# ESP32_LS7366.net
KiCad netlist of a schematic drawn in EAGLE
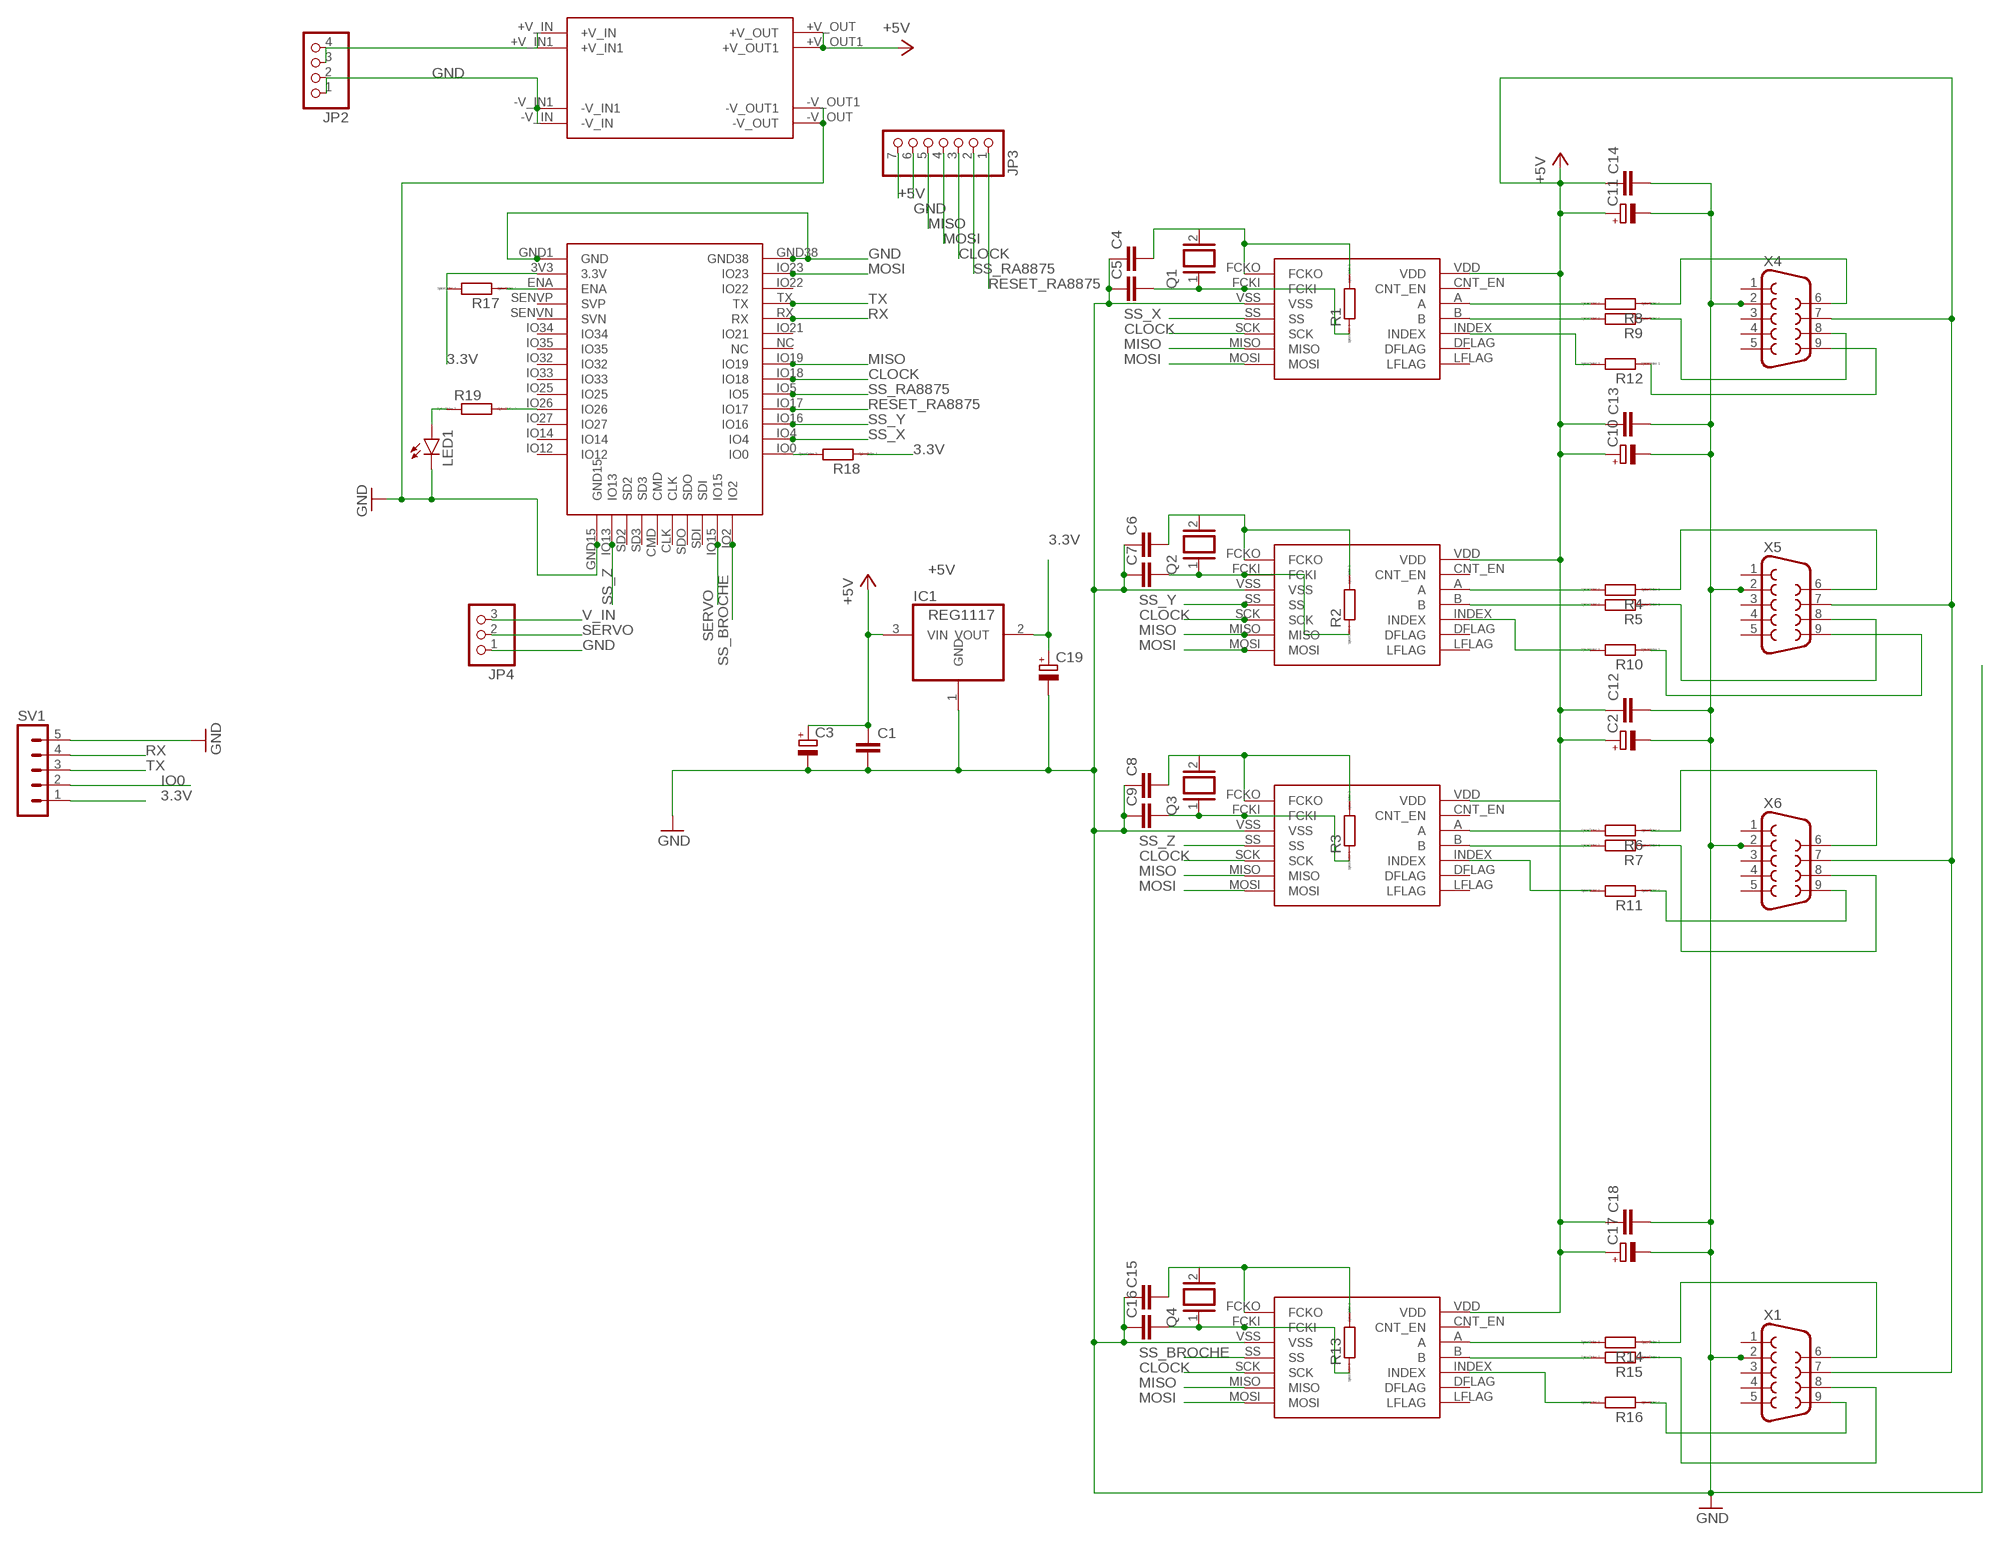
[diagram p0: schematic, sheet 1]

(export (version "E")
  (design (tool "Eeschema 10.0.6"))
  (components
    (comp (ref "C1")
      (value "C-EU050-035X075")
      (footprint "eagle-import:C050-035X075")
      (libsource (lib "eagle-import") (part "C-EU050-035X075"))
    )
    (comp (ref "C2")
      (value "CPOL-EUE5-5")
      (footprint "eagle-import:E5-5")
      (libsource (lib "eagle-import") (part "CPOL-EUE5-5"))
    )
    (comp (ref "C3")
      (value "CPOL-EUE5-5")
      (footprint "eagle-import:E5-5")
      (libsource (lib "eagle-import") (part "CPOL-EUE5-5"))
    )
    (comp (ref "C4")
      (value "C2.5/5")
      (footprint "eagle-import:C2.5-5")
      (libsource (lib "eagle-import") (part "C2.5/5"))
    )
    (comp (ref "C5")
      (value "C2.5/5")
      (footprint "eagle-import:C2.5-5")
      (libsource (lib "eagle-import") (part "C2.5/5"))
    )
    (comp (ref "C6")
      (value "C2.5/5")
      (footprint "eagle-import:C2.5-5")
      (libsource (lib "eagle-import") (part "C2.5/5"))
    )
    (comp (ref "C7")
      (value "C2.5/5")
      (footprint "eagle-import:C2.5-5")
      (libsource (lib "eagle-import") (part "C2.5/5"))
    )
    (comp (ref "C8")
      (value "C2.5/5")
      (footprint "eagle-import:C2.5-5")
      (libsource (lib "eagle-import") (part "C2.5/5"))
    )
    (comp (ref "C9")
      (value "C2.5/5")
      (footprint "eagle-import:C2.5-5")
      (libsource (lib "eagle-import") (part "C2.5/5"))
    )
    (comp (ref "C10")
      (value "CPOL-EUE5-5")
      (footprint "eagle-import:E5-5")
      (libsource (lib "eagle-import") (part "CPOL-EUE5-5"))
    )
    (comp (ref "C11")
      (value "CPOL-EUE5-5")
      (footprint "eagle-import:E5-5")
      (libsource (lib "eagle-import") (part "CPOL-EUE5-5"))
    )
    (comp (ref "C12")
      (value "C-EU050-035X075")
      (footprint "eagle-import:C050-035X075")
      (libsource (lib "eagle-import") (part "C-EU050-035X075"))
    )
    (comp (ref "C13")
      (value "C-EU050-035X075")
      (footprint "eagle-import:C050-035X075")
      (libsource (lib "eagle-import") (part "C-EU050-035X075"))
    )
    (comp (ref "C14")
      (value "C-EU050-035X075")
      (footprint "eagle-import:C050-035X075")
      (libsource (lib "eagle-import") (part "C-EU050-035X075"))
    )
    (comp (ref "C15")
      (value "C2.5/5")
      (footprint "eagle-import:C2.5-5")
      (libsource (lib "eagle-import") (part "C2.5/5"))
    )
    (comp (ref "C16")
      (value "C2.5/5")
      (footprint "eagle-import:C2.5-5")
      (libsource (lib "eagle-import") (part "C2.5/5"))
    )
    (comp (ref "C17")
      (value "CPOL-EUE5-5")
      (footprint "eagle-import:E5-5")
      (libsource (lib "eagle-import") (part "CPOL-EUE5-5"))
    )
    (comp (ref "C18")
      (value "C-EU050-035X075")
      (footprint "eagle-import:C050-035X075")
      (libsource (lib "eagle-import") (part "C-EU050-035X075"))
    )
    (comp (ref "C19")
      (value "CPOL-EUE5-5")
      (footprint "eagle-import:E5-5")
      (libsource (lib "eagle-import") (part "CPOL-EUE5-5"))
    )
    (comp (ref "IC1")
      (value "REG1117")
      (footprint "eagle-import:SOT223")
      (libsource (lib "eagle-import") (part "REG1117"))
    )
    (comp (ref "JP2")
      (value "PINHD-1X4")
      (footprint "eagle-import:1X04")
      (libsource (lib "eagle-import") (part "PINHD-1X4"))
    )
    (comp (ref "JP3")
      (value "PINHD-1X7")
      (footprint "eagle-import:1X07")
      (libsource (lib "eagle-import") (part "PINHD-1X7"))
    )
    (comp (ref "JP4")
      (value "PINHD-1X3")
      (footprint "eagle-import:1X03")
      (libsource (lib "eagle-import") (part "PINHD-1X3"))
    )
    (comp (ref "LED1")
      (value "LED3MM")
      (footprint "eagle-import:LED3MM")
      (libsource (lib "eagle-import") (part "LED3MM"))
    )
    (comp (ref "Q1")
      (value "XTAL/S")
      (footprint "eagle-import:QS")
      (libsource (lib "eagle-import") (part "XTAL/S"))
    )
    (comp (ref "Q2")
      (value "XTAL/S")
      (footprint "eagle-import:QS")
      (libsource (lib "eagle-import") (part "XTAL/S"))
    )
    (comp (ref "Q3")
      (value "XTAL/S")
      (footprint "eagle-import:QS")
      (libsource (lib "eagle-import") (part "XTAL/S"))
    )
    (comp (ref "Q4")
      (value "XTAL/S")
      (footprint "eagle-import:QS")
      (libsource (lib "eagle-import") (part "XTAL/S"))
    )
    (comp (ref "R1")
      (value "R-EU_0207_10")
      (footprint "eagle-import:0207_10")
      (libsource (lib "eagle-import") (part "R-EU_0207_10"))
    )
    (comp (ref "R2")
      (value "R-EU_0207_10")
      (footprint "eagle-import:0207_10")
      (libsource (lib "eagle-import") (part "R-EU_0207_10"))
    )
    (comp (ref "R3")
      (value "R-EU_0207_10")
      (footprint "eagle-import:0207_10")
      (libsource (lib "eagle-import") (part "R-EU_0207_10"))
    )
    (comp (ref "R4")
      (value "R-EU_0207_10")
      (footprint "eagle-import:0207_10")
      (libsource (lib "eagle-import") (part "R-EU_0207_10"))
    )
    (comp (ref "R5")
      (value "R-EU_0207_10")
      (footprint "eagle-import:0207_10")
      (libsource (lib "eagle-import") (part "R-EU_0207_10"))
    )
    (comp (ref "R6")
      (value "R-EU_0207_10")
      (footprint "eagle-import:0207_10")
      (libsource (lib "eagle-import") (part "R-EU_0207_10"))
    )
    (comp (ref "R7")
      (value "R-EU_0207_10")
      (footprint "eagle-import:0207_10")
      (libsource (lib "eagle-import") (part "R-EU_0207_10"))
    )
    (comp (ref "R8")
      (value "R-EU_0207_10")
      (footprint "eagle-import:0207_10")
      (libsource (lib "eagle-import") (part "R-EU_0207_10"))
    )
    (comp (ref "R9")
      (value "R-EU_0207_10")
      (footprint "eagle-import:0207_10")
      (libsource (lib "eagle-import") (part "R-EU_0207_10"))
    )
    (comp (ref "R10")
      (value "R-EU_0207_10")
      (footprint "eagle-import:0207_10")
      (libsource (lib "eagle-import") (part "R-EU_0207_10"))
    )
    (comp (ref "R11")
      (value "R-EU_0207_10")
      (footprint "eagle-import:0207_10")
      (libsource (lib "eagle-import") (part "R-EU_0207_10"))
    )
    (comp (ref "R12")
      (value "R-EU_0207_10")
      (footprint "eagle-import:0207_10")
      (libsource (lib "eagle-import") (part "R-EU_0207_10"))
    )
    (comp (ref "R13")
      (value "R-EU_0207_10")
      (footprint "eagle-import:0207_10")
      (libsource (lib "eagle-import") (part "R-EU_0207_10"))
    )
    (comp (ref "R14")
      (value "R-EU_0207_10")
      (footprint "eagle-import:0207_10")
      (libsource (lib "eagle-import") (part "R-EU_0207_10"))
    )
    (comp (ref "R15")
      (value "R-EU_0207_10")
      (footprint "eagle-import:0207_10")
      (libsource (lib "eagle-import") (part "R-EU_0207_10"))
    )
    (comp (ref "R16")
      (value "R-EU_0207_10")
      (footprint "eagle-import:0207_10")
      (libsource (lib "eagle-import") (part "R-EU_0207_10"))
    )
    (comp (ref "R17")
      (value "R-EU_0207_10")
      (footprint "eagle-import:0207_10")
      (libsource (lib "eagle-import") (part "R-EU_0207_10"))
    )
    (comp (ref "R18")
      (value "R-EU_0207_10")
      (footprint "eagle-import:0207_10")
      (libsource (lib "eagle-import") (part "R-EU_0207_10"))
    )
    (comp (ref "R19")
      (value "R-EU_0207_10")
      (footprint "eagle-import:0207_10")
      (libsource (lib "eagle-import") (part "R-EU_0207_10"))
    )
    (comp (ref "SV1")
      (value "MA05-1")
      (footprint "eagle-import:MA05-1")
      (libsource (lib "eagle-import") (part "MA05-1"))
    )
    (comp (ref "U$1")
      (value "LS7366")
      (footprint "eagle-import:DIP14")
      (libsource (lib "eagle-import") (part "LS7366"))
    )
    (comp (ref "U$2")
      (value "LS7366")
      (footprint "eagle-import:DIP14")
      (libsource (lib "eagle-import") (part "LS7366"))
    )
    (comp (ref "U$3")
      (value "LS7366")
      (footprint "eagle-import:DIP14")
      (libsource (lib "eagle-import") (part "LS7366"))
    )
    (comp (ref "U$4")
      (value "LS7366")
      (footprint "eagle-import:DIP14")
      (libsource (lib "eagle-import") (part "LS7366"))
    )
    (comp (ref "U$5")
      (value "MODULE5V")
      (footprint "eagle-import:MODULE5V")
      (libsource (lib "eagle-import") (part "MODULE5V"))
    )
    (comp (ref "U$6")
      (value "ESP32MODULE")
      (footprint "eagle-import:ESP32-MODULE")
      (libsource (lib "eagle-import") (part "ESP32MODULE"))
    )
    (comp (ref "X1")
      (value "F09HP")
      (footprint "eagle-import:F09HP")
      (libsource (lib "eagle-import") (part "F09HP"))
    )
    (comp (ref "X4")
      (value "F09HP")
      (footprint "eagle-import:F09HP")
      (libsource (lib "eagle-import") (part "F09HP"))
    )
    (comp (ref "X5")
      (value "F09HP")
      (footprint "eagle-import:F09HP")
      (libsource (lib "eagle-import") (part "F09HP"))
    )
    (comp (ref "X6")
      (value "F09HP")
      (footprint "eagle-import:F09HP")
      (libsource (lib "eagle-import") (part "F09HP"))
    )
  )
  (nets
    (net (code "1") (name "+5V") (class "Default")
      (node (ref "C1") (pin "1") (pinfunction "1_1") (pintype "passive"))
      (node (ref "C10") (pin "+") (pinfunction "+_+") (pintype "passive"))
      (node (ref "C11") (pin "+") (pinfunction "+_+") (pintype "passive"))
      (node (ref "C12") (pin "1") (pinfunction "1_1") (pintype "passive"))
      (node (ref "C13") (pin "1") (pinfunction "1_1") (pintype "passive"))
      (node (ref "C14") (pin "1") (pinfunction "1_1") (pintype "passive"))
      (node (ref "C17") (pin "+") (pinfunction "+_+") (pintype "passive"))
      (node (ref "C18") (pin "1") (pinfunction "1_1") (pintype "passive"))
      (node (ref "C2") (pin "+") (pinfunction "+_+") (pintype "passive"))
      (node (ref "C3") (pin "+") (pinfunction "+_+") (pintype "passive"))
      (node (ref "IC1") (pin "3") (pinfunction "VIN_3") (pintype "input"))
      (node (ref "JP3") (pin "7") (pinfunction "7_7") (pintype "passive"))
      (node (ref "U$1") (pin "VDD") (pinfunction "VDD_VDD") (pintype "bidirectional"))
      (node (ref "U$2") (pin "VDD") (pinfunction "VDD_VDD") (pintype "bidirectional"))
      (node (ref "U$3") (pin "VDD") (pinfunction "VDD_VDD") (pintype "bidirectional"))
      (node (ref "U$4") (pin "VDD") (pinfunction "VDD_VDD") (pintype "bidirectional"))
      (node (ref "U$5") (pin "+V_OUT") (pinfunction "+V_OUT_+V_OUT") (pintype "bidirectional"))
      (node (ref "U$5") (pin "+V_OUT1") (pinfunction "+V_OUT1_+V_OUT1") (pintype "bidirectional"))
      (node (ref "X1") (pin "7") (pinfunction "7_7") (pintype "passive"))
      (node (ref "X4") (pin "7") (pinfunction "7_7") (pintype "passive"))
      (node (ref "X5") (pin "7") (pinfunction "7_7") (pintype "passive"))
      (node (ref "X6") (pin "7") (pinfunction "7_7") (pintype "passive"))
    )
    (net (code "2") (name "/3.3V") (class "Default")
      (node (ref "C19") (pin "+") (pinfunction "+_+") (pintype "passive"))
      (node (ref "IC1") (pin "2") (pinfunction "VOUT_2") (pintype "output"))
      (node (ref "R17") (pin "2") (pinfunction "2_2") (pintype "passive"))
      (node (ref "R18") (pin "1") (pinfunction "1_1") (pintype "passive"))
      (node (ref "SV1") (pin "1") (pinfunction "1_1") (pintype "passive"))
      (node (ref "U$6") (pin "3V3") (pinfunction "3.3V_3V3") (pintype "bidirectional"))
    )
    (net (code "3") (name "/CLOCK") (class "Default")
      (node (ref "JP3") (pin "3") (pinfunction "3_3") (pintype "passive"))
      (node (ref "U$1") (pin "SCK") (pinfunction "SCK_SCK") (pintype "bidirectional"))
      (node (ref "U$2") (pin "SCK") (pinfunction "SCK_SCK") (pintype "bidirectional"))
      (node (ref "U$3") (pin "SCK") (pinfunction "SCK_SCK") (pintype "bidirectional"))
      (node (ref "U$4") (pin "SCK") (pinfunction "SCK_SCK") (pintype "bidirectional"))
      (node (ref "U$6") (pin "IO18") (pinfunction "IO18_IO18") (pintype "bidirectional"))
    )
    (net (code "4") (name "/IO0") (class "Default")
      (node (ref "R18") (pin "2") (pinfunction "2_2") (pintype "passive"))
      (node (ref "SV1") (pin "2") (pinfunction "2_2") (pintype "passive"))
      (node (ref "U$6") (pin "IO0") (pinfunction "IO0_IO0") (pintype "bidirectional"))
    )
    (net (code "5") (name "/MISO") (class "Default")
      (node (ref "JP3") (pin "5") (pinfunction "5_5") (pintype "passive"))
      (node (ref "U$1") (pin "MISO") (pinfunction "MISO_MISO") (pintype "bidirectional"))
      (node (ref "U$2") (pin "MISO") (pinfunction "MISO_MISO") (pintype "bidirectional"))
      (node (ref "U$3") (pin "MISO") (pinfunction "MISO_MISO") (pintype "bidirectional"))
      (node (ref "U$4") (pin "MISO") (pinfunction "MISO_MISO") (pintype "bidirectional"))
      (node (ref "U$6") (pin "IO19") (pinfunction "IO19_IO19") (pintype "bidirectional"))
    )
    (net (code "6") (name "/MOSI") (class "Default")
      (node (ref "JP3") (pin "4") (pinfunction "4_4") (pintype "passive"))
      (node (ref "U$1") (pin "MOSI") (pinfunction "MOSI_MOSI") (pintype "bidirectional"))
      (node (ref "U$2") (pin "MOSI") (pinfunction "MOSI_MOSI") (pintype "bidirectional"))
      (node (ref "U$3") (pin "MOSI") (pinfunction "MOSI_MOSI") (pintype "bidirectional"))
      (node (ref "U$4") (pin "MOSI") (pinfunction "MOSI_MOSI") (pintype "bidirectional"))
      (node (ref "U$6") (pin "IO23") (pinfunction "IO23_IO23") (pintype "bidirectional"))
    )
    (net (code "7") (name "/RESET_RA8875") (class "Default")
      (node (ref "JP3") (pin "1") (pinfunction "1_1") (pintype "passive"))
      (node (ref "U$6") (pin "IO17") (pinfunction "IO17_IO17") (pintype "bidirectional"))
    )
    (net (code "8") (name "/RX") (class "Default")
      (node (ref "SV1") (pin "4") (pinfunction "4_4") (pintype "passive"))
      (node (ref "U$6") (pin "RX") (pinfunction "RX_RX") (pintype "bidirectional"))
    )
    (net (code "9") (name "/SERVO") (class "Default")
      (node (ref "JP4") (pin "2") (pinfunction "2_2") (pintype "passive"))
      (node (ref "U$6") (pin "IO15") (pinfunction "IO15_IO15") (pintype "bidirectional"))
    )
    (net (code "10") (name "/SS_BROCHE") (class "Default")
      (node (ref "U$1") (pin "SS") (pinfunction "SS_SS") (pintype "bidirectional"))
      (node (ref "U$6") (pin "IO2") (pinfunction "IO2_IO2") (pintype "bidirectional"))
    )
    (net (code "11") (name "/SS_RA8875") (class "Default")
      (node (ref "JP3") (pin "2") (pinfunction "2_2") (pintype "passive"))
      (node (ref "U$6") (pin "IO5") (pinfunction "IO5_IO5") (pintype "bidirectional"))
    )
    (net (code "12") (name "/SS_X") (class "Default")
      (node (ref "U$2") (pin "SS") (pinfunction "SS_SS") (pintype "bidirectional"))
      (node (ref "U$6") (pin "IO4") (pinfunction "IO4_IO4") (pintype "bidirectional"))
    )
    (net (code "13") (name "/SS_Y") (class "Default")
      (node (ref "U$3") (pin "SS") (pinfunction "SS_SS") (pintype "bidirectional"))
      (node (ref "U$6") (pin "IO16") (pinfunction "IO16_IO16") (pintype "bidirectional"))
    )
    (net (code "14") (name "/SS_Z") (class "Default")
      (node (ref "U$4") (pin "SS") (pinfunction "SS_SS") (pintype "bidirectional"))
      (node (ref "U$6") (pin "IO13") (pinfunction "IO13_IO13") (pintype "bidirectional"))
    )
    (net (code "15") (name "/TX") (class "Default")
      (node (ref "SV1") (pin "3") (pinfunction "3_3") (pintype "passive"))
      (node (ref "U$6") (pin "TX") (pinfunction "TX_TX") (pintype "bidirectional"))
    )
    (net (code "16") (name "/V_IN") (class "Default")
      (node (ref "JP2") (pin "3") (pinfunction "3_3") (pintype "passive"))
      (node (ref "JP2") (pin "4") (pinfunction "4_4") (pintype "passive"))
      (node (ref "JP4") (pin "3") (pinfunction "3_3") (pintype "passive"))
      (node (ref "U$5") (pin "+V_IN") (pinfunction "+V_IN_+V_IN") (pintype "bidirectional"))
      (node (ref "U$5") (pin "+V_IN1") (pinfunction "+V_IN1_+V_IN1") (pintype "bidirectional"))
    )
    (net (code "17") (name "GND") (class "Default")
      (node (ref "C1") (pin "2") (pinfunction "2_2") (pintype "passive"))
      (node (ref "C10") (pin "-") (pinfunction "-_-") (pintype "passive"))
      (node (ref "C11") (pin "-") (pinfunction "-_-") (pintype "passive"))
      (node (ref "C12") (pin "2") (pinfunction "2_2") (pintype "passive"))
      (node (ref "C13") (pin "2") (pinfunction "2_2") (pintype "passive"))
      (node (ref "C14") (pin "2") (pinfunction "2_2") (pintype "passive"))
      (node (ref "C15") (pin "1") (pinfunction "1_1") (pintype "passive"))
      (node (ref "C16") (pin "1") (pinfunction "1_1") (pintype "passive"))
      (node (ref "C17") (pin "-") (pinfunction "-_-") (pintype "passive"))
      (node (ref "C18") (pin "2") (pinfunction "2_2") (pintype "passive"))
      (node (ref "C19") (pin "-") (pinfunction "-_-") (pintype "passive"))
      (node (ref "C2") (pin "-") (pinfunction "-_-") (pintype "passive"))
      (node (ref "C3") (pin "-") (pinfunction "-_-") (pintype "passive"))
      (node (ref "C4") (pin "1") (pinfunction "1_1") (pintype "passive"))
      (node (ref "C5") (pin "1") (pinfunction "1_1") (pintype "passive"))
      (node (ref "C6") (pin "1") (pinfunction "1_1") (pintype "passive"))
      (node (ref "C7") (pin "1") (pinfunction "1_1") (pintype "passive"))
      (node (ref "C8") (pin "1") (pinfunction "1_1") (pintype "passive"))
      (node (ref "C9") (pin "1") (pinfunction "1_1") (pintype "passive"))
      (node (ref "IC1") (pin "1") (pinfunction "GND_1") (pintype "power_in"))
      (node (ref "JP2") (pin "1") (pinfunction "1_1") (pintype "passive"))
      (node (ref "JP2") (pin "2") (pinfunction "2_2") (pintype "passive"))
      (node (ref "JP3") (pin "6") (pinfunction "6_6") (pintype "passive"))
      (node (ref "JP4") (pin "1") (pinfunction "1_1") (pintype "passive"))
      (node (ref "LED1") (pin "K") (pinfunction "C_K") (pintype "passive"))
      (node (ref "SV1") (pin "5") (pinfunction "5_5") (pintype "passive"))
      (node (ref "U$1") (pin "VSS") (pinfunction "VSS_VSS") (pintype "bidirectional"))
      (node (ref "U$2") (pin "VSS") (pinfunction "VSS_VSS") (pintype "bidirectional"))
      (node (ref "U$3") (pin "VSS") (pinfunction "VSS_VSS") (pintype "bidirectional"))
      (node (ref "U$4") (pin "VSS") (pinfunction "VSS_VSS") (pintype "bidirectional"))
      (node (ref "U$5") (pin "-V_IN") (pinfunction "-V_IN_-V_IN") (pintype "bidirectional"))
      (node (ref "U$5") (pin "-V_IN1") (pinfunction "-V_IN1_-V_IN1") (pintype "bidirectional"))
      (node (ref "U$5") (pin "-V_OUT") (pinfunction "-V_OUT_-V_OUT") (pintype "bidirectional"))
      (node (ref "U$5") (pin "-V_OUT1") (pinfunction "-V_OUT1_-V_OUT1") (pintype "bidirectional"))
      (node (ref "U$6") (pin "GND1") (pinfunction "GND_GND1") (pintype "bidirectional"))
      (node (ref "U$6") (pin "GND15") (pinfunction "GND15_GND15") (pintype "bidirectional"))
      (node (ref "U$6") (pin "GND38") (pinfunction "GND38_GND38") (pintype "bidirectional"))
      (node (ref "X1") (pin "2") (pinfunction "2_2") (pintype "passive"))
      (node (ref "X4") (pin "2") (pinfunction "2_2") (pintype "passive"))
      (node (ref "X5") (pin "2") (pinfunction "2_2") (pintype "passive"))
      (node (ref "X6") (pin "2") (pinfunction "2_2") (pintype "passive"))
    )
    (net (code "18") (name "Net-(C4-Pad2)") (class "Default")
      (node (ref "C4") (pin "2") (pinfunction "2_2") (pintype "passive"))
      (node (ref "Q1") (pin "2") (pinfunction "2_2") (pintype "passive"))
      (node (ref "R1") (pin "2") (pinfunction "2_2") (pintype "passive"))
      (node (ref "U$2") (pin "FCKO") (pinfunction "FCKO_FCKO") (pintype "bidirectional"))
    )
    (net (code "19") (name "Net-(C5-Pad2)") (class "Default")
      (node (ref "C5") (pin "2") (pinfunction "2_2") (pintype "passive"))
      (node (ref "Q1") (pin "1") (pinfunction "1_1") (pintype "passive"))
      (node (ref "R1") (pin "1") (pinfunction "1_1") (pintype "passive"))
      (node (ref "U$2") (pin "FCKI") (pinfunction "FCKI_FCKI") (pintype "bidirectional"))
    )
    (net (code "20") (name "Net-(C6-Pad2)") (class "Default")
      (node (ref "C6") (pin "2") (pinfunction "2_2") (pintype "passive"))
      (node (ref "Q2") (pin "2") (pinfunction "2_2") (pintype "passive"))
      (node (ref "R2") (pin "2") (pinfunction "2_2") (pintype "passive"))
      (node (ref "U$3") (pin "FCKO") (pinfunction "FCKO_FCKO") (pintype "bidirectional"))
    )
    (net (code "21") (name "Net-(C7-Pad2)") (class "Default")
      (node (ref "C7") (pin "2") (pinfunction "2_2") (pintype "passive"))
      (node (ref "Q2") (pin "1") (pinfunction "1_1") (pintype "passive"))
      (node (ref "R2") (pin "1") (pinfunction "1_1") (pintype "passive"))
      (node (ref "U$3") (pin "FCKI") (pinfunction "FCKI_FCKI") (pintype "bidirectional"))
    )
    (net (code "22") (name "Net-(C8-Pad2)") (class "Default")
      (node (ref "C8") (pin "2") (pinfunction "2_2") (pintype "passive"))
      (node (ref "Q3") (pin "2") (pinfunction "2_2") (pintype "passive"))
      (node (ref "R3") (pin "2") (pinfunction "2_2") (pintype "passive"))
      (node (ref "U$4") (pin "FCKO") (pinfunction "FCKO_FCKO") (pintype "bidirectional"))
    )
    (net (code "23") (name "Net-(C9-Pad2)") (class "Default")
      (node (ref "C9") (pin "2") (pinfunction "2_2") (pintype "passive"))
      (node (ref "Q3") (pin "1") (pinfunction "1_1") (pintype "passive"))
      (node (ref "R3") (pin "1") (pinfunction "1_1") (pintype "passive"))
      (node (ref "U$4") (pin "FCKI") (pinfunction "FCKI_FCKI") (pintype "bidirectional"))
    )
    (net (code "24") (name "Net-(C15-Pad2)") (class "Default")
      (node (ref "C15") (pin "2") (pinfunction "2_2") (pintype "passive"))
      (node (ref "Q4") (pin "2") (pinfunction "2_2") (pintype "passive"))
      (node (ref "R13") (pin "2") (pinfunction "2_2") (pintype "passive"))
      (node (ref "U$1") (pin "FCKO") (pinfunction "FCKO_FCKO") (pintype "bidirectional"))
    )
    (net (code "25") (name "Net-(C16-Pad2)") (class "Default")
      (node (ref "C16") (pin "2") (pinfunction "2_2") (pintype "passive"))
      (node (ref "Q4") (pin "1") (pinfunction "1_1") (pintype "passive"))
      (node (ref "R13") (pin "1") (pinfunction "1_1") (pintype "passive"))
      (node (ref "U$1") (pin "FCKI") (pinfunction "FCKI_FCKI") (pintype "bidirectional"))
    )
    (net (code "26") (name "Net-(LED1-PadA)") (class "Default")
      (node (ref "LED1") (pin "A") (pinfunction "A_A") (pintype "passive"))
      (node (ref "R19") (pin "1") (pinfunction "1_1") (pintype "passive"))
    )
    (net (code "27") (name "Net-(R4-Pad1)") (class "Default")
      (node (ref "R4") (pin "1") (pinfunction "1_1") (pintype "passive"))
      (node (ref "X5") (pin "6") (pinfunction "6_6") (pintype "passive"))
    )
    (net (code "28") (name "Net-(R4-Pad2)") (class "Default")
      (node (ref "R4") (pin "2") (pinfunction "2_2") (pintype "passive"))
      (node (ref "U$3") (pin "A") (pinfunction "A_A") (pintype "bidirectional"))
    )
    (net (code "29") (name "Net-(R5-Pad1)") (class "Default")
      (node (ref "R5") (pin "1") (pinfunction "1_1") (pintype "passive"))
      (node (ref "X5") (pin "8") (pinfunction "8_8") (pintype "passive"))
    )
    (net (code "30") (name "Net-(R5-Pad2)") (class "Default")
      (node (ref "R5") (pin "2") (pinfunction "2_2") (pintype "passive"))
      (node (ref "U$3") (pin "B") (pinfunction "B_B") (pintype "bidirectional"))
    )
    (net (code "31") (name "Net-(R6-Pad1)") (class "Default")
      (node (ref "R6") (pin "1") (pinfunction "1_1") (pintype "passive"))
      (node (ref "X6") (pin "6") (pinfunction "6_6") (pintype "passive"))
    )
    (net (code "32") (name "Net-(R6-Pad2)") (class "Default")
      (node (ref "R6") (pin "2") (pinfunction "2_2") (pintype "passive"))
      (node (ref "U$4") (pin "A") (pinfunction "A_A") (pintype "bidirectional"))
    )
    (net (code "33") (name "Net-(R7-Pad1)") (class "Default")
      (node (ref "R7") (pin "1") (pinfunction "1_1") (pintype "passive"))
      (node (ref "X6") (pin "8") (pinfunction "8_8") (pintype "passive"))
    )
    (net (code "34") (name "Net-(R7-Pad2)") (class "Default")
      (node (ref "R7") (pin "2") (pinfunction "2_2") (pintype "passive"))
      (node (ref "U$4") (pin "B") (pinfunction "B_B") (pintype "bidirectional"))
    )
    (net (code "35") (name "Net-(R8-Pad1)") (class "Default")
      (node (ref "R8") (pin "1") (pinfunction "1_1") (pintype "passive"))
      (node (ref "X4") (pin "6") (pinfunction "6_6") (pintype "passive"))
    )
    (net (code "36") (name "Net-(R8-Pad2)") (class "Default")
      (node (ref "R8") (pin "2") (pinfunction "2_2") (pintype "passive"))
      (node (ref "U$2") (pin "A") (pinfunction "A_A") (pintype "bidirectional"))
    )
    (net (code "37") (name "Net-(R9-Pad1)") (class "Default")
      (node (ref "R9") (pin "1") (pinfunction "1_1") (pintype "passive"))
      (node (ref "X4") (pin "8") (pinfunction "8_8") (pintype "passive"))
    )
    (net (code "38") (name "Net-(R9-Pad2)") (class "Default")
      (node (ref "R9") (pin "2") (pinfunction "2_2") (pintype "passive"))
      (node (ref "U$2") (pin "B") (pinfunction "B_B") (pintype "bidirectional"))
    )
    (net (code "39") (name "Net-(R10-Pad1)") (class "Default")
      (node (ref "R10") (pin "1") (pinfunction "1_1") (pintype "passive"))
      (node (ref "X5") (pin "9") (pinfunction "9_9") (pintype "passive"))
    )
    (net (code "40") (name "Net-(R10-Pad2)") (class "Default")
      (node (ref "R10") (pin "2") (pinfunction "2_2") (pintype "passive"))
      (node (ref "U$3") (pin "INDEX") (pinfunction "INDEX_INDEX") (pintype "bidirectional"))
    )
    (net (code "41") (name "Net-(R11-Pad1)") (class "Default")
      (node (ref "R11") (pin "1") (pinfunction "1_1") (pintype "passive"))
      (node (ref "X6") (pin "9") (pinfunction "9_9") (pintype "passive"))
    )
    (net (code "42") (name "Net-(R11-Pad2)") (class "Default")
      (node (ref "R11") (pin "2") (pinfunction "2_2") (pintype "passive"))
      (node (ref "U$4") (pin "INDEX") (pinfunction "INDEX_INDEX") (pintype "bidirectional"))
    )
    (net (code "43") (name "Net-(R12-Pad1)") (class "Default")
      (node (ref "R12") (pin "1") (pinfunction "1_1") (pintype "passive"))
      (node (ref "X4") (pin "9") (pinfunction "9_9") (pintype "passive"))
    )
    (net (code "44") (name "Net-(R12-Pad2)") (class "Default")
      (node (ref "R12") (pin "2") (pinfunction "2_2") (pintype "passive"))
      (node (ref "U$2") (pin "INDEX") (pinfunction "INDEX_INDEX") (pintype "bidirectional"))
    )
    (net (code "45") (name "Net-(R14-Pad1)") (class "Default")
      (node (ref "R14") (pin "1") (pinfunction "1_1") (pintype "passive"))
      (node (ref "X1") (pin "6") (pinfunction "6_6") (pintype "passive"))
    )
    (net (code "46") (name "Net-(R14-Pad2)") (class "Default")
      (node (ref "R14") (pin "2") (pinfunction "2_2") (pintype "passive"))
      (node (ref "U$1") (pin "A") (pinfunction "A_A") (pintype "bidirectional"))
    )
    (net (code "47") (name "Net-(R15-Pad1)") (class "Default")
      (node (ref "R15") (pin "1") (pinfunction "1_1") (pintype "passive"))
      (node (ref "X1") (pin "8") (pinfunction "8_8") (pintype "passive"))
    )
    (net (code "48") (name "Net-(R15-Pad2)") (class "Default")
      (node (ref "R15") (pin "2") (pinfunction "2_2") (pintype "passive"))
      (node (ref "U$1") (pin "B") (pinfunction "B_B") (pintype "bidirectional"))
    )
    (net (code "49") (name "Net-(R16-Pad1)") (class "Default")
      (node (ref "R16") (pin "1") (pinfunction "1_1") (pintype "passive"))
      (node (ref "X1") (pin "9") (pinfunction "9_9") (pintype "passive"))
    )
    (net (code "50") (name "Net-(R16-Pad2)") (class "Default")
      (node (ref "R16") (pin "2") (pinfunction "2_2") (pintype "passive"))
      (node (ref "U$1") (pin "INDEX") (pinfunction "INDEX_INDEX") (pintype "bidirectional"))
    )
    (net (code "51") (name "Net-(R17-Pad1)") (class "Default")
      (node (ref "R17") (pin "1") (pinfunction "1_1") (pintype "passive"))
      (node (ref "U$6") (pin "ENA") (pinfunction "ENA_ENA") (pintype "bidirectional"))
    )
    (net (code "52") (name "Net-(R19-Pad2)") (class "Default")
      (node (ref "R19") (pin "2") (pinfunction "2_2") (pintype "passive"))
      (node (ref "U$6") (pin "IO26") (pinfunction "IO26_IO26") (pintype "bidirectional"))
    )
    (net (code "53") (name "unconnected-(U$1-PadCNT_EN)") (class "Default")
      (node (ref "U$1") (pin "CNT_EN") (pinfunction "CNT_EN_CNT_EN") (pintype "bidirectional"))
    )
    (net (code "54") (name "unconnected-(U$1-PadDFLAG)") (class "Default")
      (node (ref "U$1") (pin "DFLAG") (pinfunction "DFLAG_DFLAG") (pintype "bidirectional"))
    )
    (net (code "55") (name "unconnected-(U$1-PadLFLAG)") (class "Default")
      (node (ref "U$1") (pin "LFLAG") (pinfunction "LFLAG_LFLAG") (pintype "bidirectional"))
    )
    (net (code "56") (name "unconnected-(U$2-PadCNT_EN)") (class "Default")
      (node (ref "U$2") (pin "CNT_EN") (pinfunction "CNT_EN_CNT_EN") (pintype "bidirectional"))
    )
    (net (code "57") (name "unconnected-(U$2-PadDFLAG)") (class "Default")
      (node (ref "U$2") (pin "DFLAG") (pinfunction "DFLAG_DFLAG") (pintype "bidirectional"))
    )
    (net (code "58") (name "unconnected-(U$2-PadLFLAG)") (class "Default")
      (node (ref "U$2") (pin "LFLAG") (pinfunction "LFLAG_LFLAG") (pintype "bidirectional"))
    )
    (net (code "59") (name "unconnected-(U$3-PadCNT_EN)") (class "Default")
      (node (ref "U$3") (pin "CNT_EN") (pinfunction "CNT_EN_CNT_EN") (pintype "bidirectional"))
    )
    (net (code "60") (name "unconnected-(U$3-PadDFLAG)") (class "Default")
      (node (ref "U$3") (pin "DFLAG") (pinfunction "DFLAG_DFLAG") (pintype "bidirectional"))
    )
    (net (code "61") (name "unconnected-(U$3-PadLFLAG)") (class "Default")
      (node (ref "U$3") (pin "LFLAG") (pinfunction "LFLAG_LFLAG") (pintype "bidirectional"))
    )
    (net (code "62") (name "unconnected-(U$4-PadCNT_EN)") (class "Default")
      (node (ref "U$4") (pin "CNT_EN") (pinfunction "CNT_EN_CNT_EN") (pintype "bidirectional"))
    )
    (net (code "63") (name "unconnected-(U$4-PadDFLAG)") (class "Default")
      (node (ref "U$4") (pin "DFLAG") (pinfunction "DFLAG_DFLAG") (pintype "bidirectional"))
    )
    (net (code "64") (name "unconnected-(U$4-PadLFLAG)") (class "Default")
      (node (ref "U$4") (pin "LFLAG") (pinfunction "LFLAG_LFLAG") (pintype "bidirectional"))
    )
    (net (code "65") (name "unconnected-(U$6-PadCLK)") (class "Default")
      (node (ref "U$6") (pin "CLK") (pinfunction "CLK_CLK") (pintype "bidirectional"))
    )
    (net (code "66") (name "unconnected-(U$6-PadCMD)") (class "Default")
      (node (ref "U$6") (pin "CMD") (pinfunction "CMD_CMD") (pintype "bidirectional"))
    )
    (net (code "67") (name "unconnected-(U$6-PadIO12)") (class "Default")
      (node (ref "U$6") (pin "IO12") (pinfunction "IO12_IO12") (pintype "bidirectional"))
    )
    (net (code "68") (name "unconnected-(U$6-PadIO14)") (class "Default")
      (node (ref "U$6") (pin "IO14") (pinfunction "IO14_IO14") (pintype "bidirectional"))
    )
    (net (code "69") (name "unconnected-(U$6-PadIO21)") (class "Default")
      (node (ref "U$6") (pin "IO21") (pinfunction "IO21_IO21") (pintype "bidirectional"))
    )
    (net (code "70") (name "unconnected-(U$6-PadIO22)") (class "Default")
      (node (ref "U$6") (pin "IO22") (pinfunction "IO22_IO22") (pintype "bidirectional"))
    )
    (net (code "71") (name "unconnected-(U$6-PadIO25)") (class "Default")
      (node (ref "U$6") (pin "IO25") (pinfunction "IO25_IO25") (pintype "bidirectional"))
    )
    (net (code "72") (name "unconnected-(U$6-PadIO27)") (class "Default")
      (node (ref "U$6") (pin "IO27") (pinfunction "IO27_IO27") (pintype "bidirectional"))
    )
    (net (code "73") (name "unconnected-(U$6-PadIO32)") (class "Default")
      (node (ref "U$6") (pin "IO32") (pinfunction "IO32_IO32") (pintype "bidirectional"))
    )
    (net (code "74") (name "unconnected-(U$6-PadIO33)") (class "Default")
      (node (ref "U$6") (pin "IO33") (pinfunction "IO33_IO33") (pintype "bidirectional"))
    )
    (net (code "75") (name "unconnected-(U$6-PadIO34)") (class "Default")
      (node (ref "U$6") (pin "IO34") (pinfunction "IO34_IO34") (pintype "bidirectional"))
    )
    (net (code "76") (name "unconnected-(U$6-PadIO35)") (class "Default")
      (node (ref "U$6") (pin "IO35") (pinfunction "IO35_IO35") (pintype "bidirectional"))
    )
    (net (code "77") (name "unconnected-(U$6-PadNC)") (class "Default")
      (node (ref "U$6") (pin "NC") (pinfunction "NC_NC") (pintype "bidirectional"))
    )
    (net (code "78") (name "unconnected-(U$6-PadSD2)") (class "Default")
      (node (ref "U$6") (pin "SD2") (pinfunction "SD2_SD2") (pintype "bidirectional"))
    )
    (net (code "79") (name "unconnected-(U$6-PadSD3)") (class "Default")
      (node (ref "U$6") (pin "SD3") (pinfunction "SD3_SD3") (pintype "bidirectional"))
    )
    (net (code "80") (name "unconnected-(U$6-PadSDI)") (class "Default")
      (node (ref "U$6") (pin "SDI") (pinfunction "SDI_SDI") (pintype "bidirectional"))
    )
    (net (code "81") (name "unconnected-(U$6-PadSDO)") (class "Default")
      (node (ref "U$6") (pin "SDO") (pinfunction "SDO_SDO") (pintype "bidirectional"))
    )
    (net (code "82") (name "unconnected-(U$6-SVN-PadSENVN)") (class "Default")
      (node (ref "U$6") (pin "SENVN") (pinfunction "SVN_SENVN") (pintype "bidirectional"))
    )
    (net (code "83") (name "unconnected-(U$6-SVP-PadSENVP)") (class "Default")
      (node (ref "U$6") (pin "SENVP") (pinfunction "SVP_SENVP") (pintype "bidirectional"))
    )
    (net (code "84") (name "unconnected-(X1-Pad1)") (class "Default")
      (node (ref "X1") (pin "1") (pinfunction "1_1") (pintype "passive"))
    )
    (net (code "85") (name "unconnected-(X1-Pad3)") (class "Default")
      (node (ref "X1") (pin "3") (pinfunction "3_3") (pintype "passive"))
    )
    (net (code "86") (name "unconnected-(X1-Pad4)") (class "Default")
      (node (ref "X1") (pin "4") (pinfunction "4_4") (pintype "passive"))
    )
    (net (code "87") (name "unconnected-(X1-Pad5)") (class "Default")
      (node (ref "X1") (pin "5") (pinfunction "5_5") (pintype "passive"))
    )
    (net (code "88") (name "unconnected-(X4-Pad1)") (class "Default")
      (node (ref "X4") (pin "1") (pinfunction "1_1") (pintype "passive"))
    )
    (net (code "89") (name "unconnected-(X4-Pad3)") (class "Default")
      (node (ref "X4") (pin "3") (pinfunction "3_3") (pintype "passive"))
    )
    (net (code "90") (name "unconnected-(X4-Pad4)") (class "Default")
      (node (ref "X4") (pin "4") (pinfunction "4_4") (pintype "passive"))
    )
    (net (code "91") (name "unconnected-(X4-Pad5)") (class "Default")
      (node (ref "X4") (pin "5") (pinfunction "5_5") (pintype "passive"))
    )
    (net (code "92") (name "unconnected-(X5-Pad1)") (class "Default")
      (node (ref "X5") (pin "1") (pinfunction "1_1") (pintype "passive"))
    )
    (net (code "93") (name "unconnected-(X5-Pad3)") (class "Default")
      (node (ref "X5") (pin "3") (pinfunction "3_3") (pintype "passive"))
    )
    (net (code "94") (name "unconnected-(X5-Pad4)") (class "Default")
      (node (ref "X5") (pin "4") (pinfunction "4_4") (pintype "passive"))
    )
    (net (code "95") (name "unconnected-(X5-Pad5)") (class "Default")
      (node (ref "X5") (pin "5") (pinfunction "5_5") (pintype "passive"))
    )
    (net (code "96") (name "unconnected-(X6-Pad1)") (class "Default")
      (node (ref "X6") (pin "1") (pinfunction "1_1") (pintype "passive"))
    )
    (net (code "97") (name "unconnected-(X6-Pad3)") (class "Default")
      (node (ref "X6") (pin "3") (pinfunction "3_3") (pintype "passive"))
    )
    (net (code "98") (name "unconnected-(X6-Pad4)") (class "Default")
      (node (ref "X6") (pin "4") (pinfunction "4_4") (pintype "passive"))
    )
    (net (code "99") (name "unconnected-(X6-Pad5)") (class "Default")
      (node (ref "X6") (pin "5") (pinfunction "5_5") (pintype "passive"))
    )
  )
)
